# ESP-12_Breakout_SMT.net
KiCad netlist of a schematic drawn in EAGLE
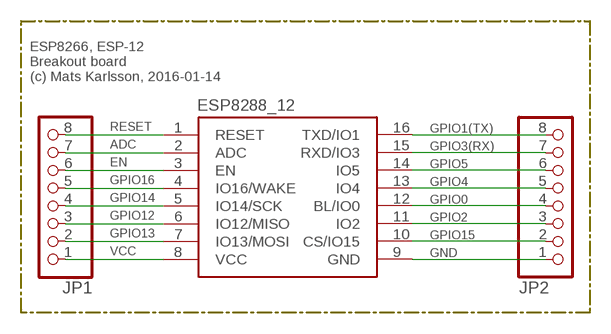
[diagram p0: schematic, sheet 1]

(export (version "E")
  (design (tool "Eeschema 10.0.6"))
  (components
    (comp (ref "ESP8288_12")
      (value "ESP8266-12")
      (footprint "eagle-import:ESP8266-12")
      (libsource (lib "eagle-import") (part "ESP8266-12"))
    )
    (comp (ref "JP1")
      (value "PINHD-1X81X08_SMT")
      (footprint "eagle-import:1X08_SMT")
      (libsource (lib "eagle-import") (part "PINHD-1X81X08_SMT"))
    )
    (comp (ref "JP2")
      (value "PINHD-1X81X08_SMT")
      (footprint "eagle-import:1X08_SMT")
      (libsource (lib "eagle-import") (part "PINHD-1X81X08_SMT"))
    )
  )
  (nets
    (net (code "1") (name "/ADC") (class "Default")
      (node (ref "ESP8288_12") (pin "2") (pinfunction "ADC_2") (pintype "bidirectional"))
      (node (ref "JP1") (pin "7") (pinfunction "7_7") (pintype "passive"))
    )
    (net (code "2") (name "/EN") (class "Default")
      (node (ref "ESP8288_12") (pin "3") (pinfunction "EN_3") (pintype "bidirectional"))
      (node (ref "JP1") (pin "6") (pinfunction "6_6") (pintype "passive"))
    )
    (net (code "3") (name "/GND") (class "Default")
      (node (ref "ESP8288_12") (pin "9") (pinfunction "GND_9") (pintype "power_in"))
      (node (ref "JP2") (pin "1") (pinfunction "1_1") (pintype "passive"))
    )
    (net (code "4") (name "/GPIO0") (class "Default")
      (node (ref "ESP8288_12") (pin "12") (pinfunction "BL/IO0_12") (pintype "bidirectional"))
      (node (ref "JP2") (pin "4") (pinfunction "4_4") (pintype "passive"))
    )
    (net (code "5") (name "/GPIO1(TX)") (class "Default")
      (node (ref "ESP8288_12") (pin "16") (pinfunction "TXD/IO1_16") (pintype "bidirectional"))
      (node (ref "JP2") (pin "8") (pinfunction "8_8") (pintype "passive"))
    )
    (net (code "6") (name "/GPIO2") (class "Default")
      (node (ref "ESP8288_12") (pin "11") (pinfunction "IO2_11") (pintype "bidirectional"))
      (node (ref "JP2") (pin "3") (pinfunction "3_3") (pintype "passive"))
    )
    (net (code "7") (name "/GPIO3(RX)") (class "Default")
      (node (ref "ESP8288_12") (pin "15") (pinfunction "RXD/IO3_15") (pintype "bidirectional"))
      (node (ref "JP2") (pin "7") (pinfunction "7_7") (pintype "passive"))
    )
    (net (code "8") (name "/GPIO4") (class "Default")
      (node (ref "ESP8288_12") (pin "13") (pinfunction "IO4_13") (pintype "bidirectional"))
      (node (ref "JP2") (pin "5") (pinfunction "5_5") (pintype "passive"))
    )
    (net (code "9") (name "/GPIO5") (class "Default")
      (node (ref "ESP8288_12") (pin "14") (pinfunction "IO5_14") (pintype "bidirectional"))
      (node (ref "JP2") (pin "6") (pinfunction "6_6") (pintype "passive"))
    )
    (net (code "10") (name "/GPIO12") (class "Default")
      (node (ref "ESP8288_12") (pin "6") (pinfunction "IO12/MISO_6") (pintype "bidirectional"))
      (node (ref "JP1") (pin "3") (pinfunction "3_3") (pintype "passive"))
    )
    (net (code "11") (name "/GPIO13") (class "Default")
      (node (ref "ESP8288_12") (pin "7") (pinfunction "IO13/MOSI_7") (pintype "bidirectional"))
      (node (ref "JP1") (pin "2") (pinfunction "2_2") (pintype "passive"))
    )
    (net (code "12") (name "/GPIO14") (class "Default")
      (node (ref "ESP8288_12") (pin "5") (pinfunction "IO14/SCK_5") (pintype "bidirectional"))
      (node (ref "JP1") (pin "4") (pinfunction "4_4") (pintype "passive"))
    )
    (net (code "13") (name "/GPIO15") (class "Default")
      (node (ref "ESP8288_12") (pin "10") (pinfunction "CS/IO15_10") (pintype "bidirectional"))
      (node (ref "JP2") (pin "2") (pinfunction "2_2") (pintype "passive"))
    )
    (net (code "14") (name "/GPIO16") (class "Default")
      (node (ref "ESP8288_12") (pin "4") (pinfunction "IO16/WAKE_4") (pintype "bidirectional"))
      (node (ref "JP1") (pin "5") (pinfunction "5_5") (pintype "passive"))
    )
    (net (code "15") (name "/RESET") (class "Default")
      (node (ref "ESP8288_12") (pin "1") (pinfunction "RESET_1") (pintype "bidirectional"))
      (node (ref "JP1") (pin "8") (pinfunction "8_8") (pintype "passive"))
    )
    (net (code "16") (name "/VCC") (class "Default")
      (node (ref "ESP8288_12") (pin "8") (pinfunction "VCC_8") (pintype "power_in"))
      (node (ref "JP1") (pin "1") (pinfunction "1_1") (pintype "passive"))
    )
  )
)
